# new_inverter.net
KiCad netlist of a schematic drawn in EAGLE
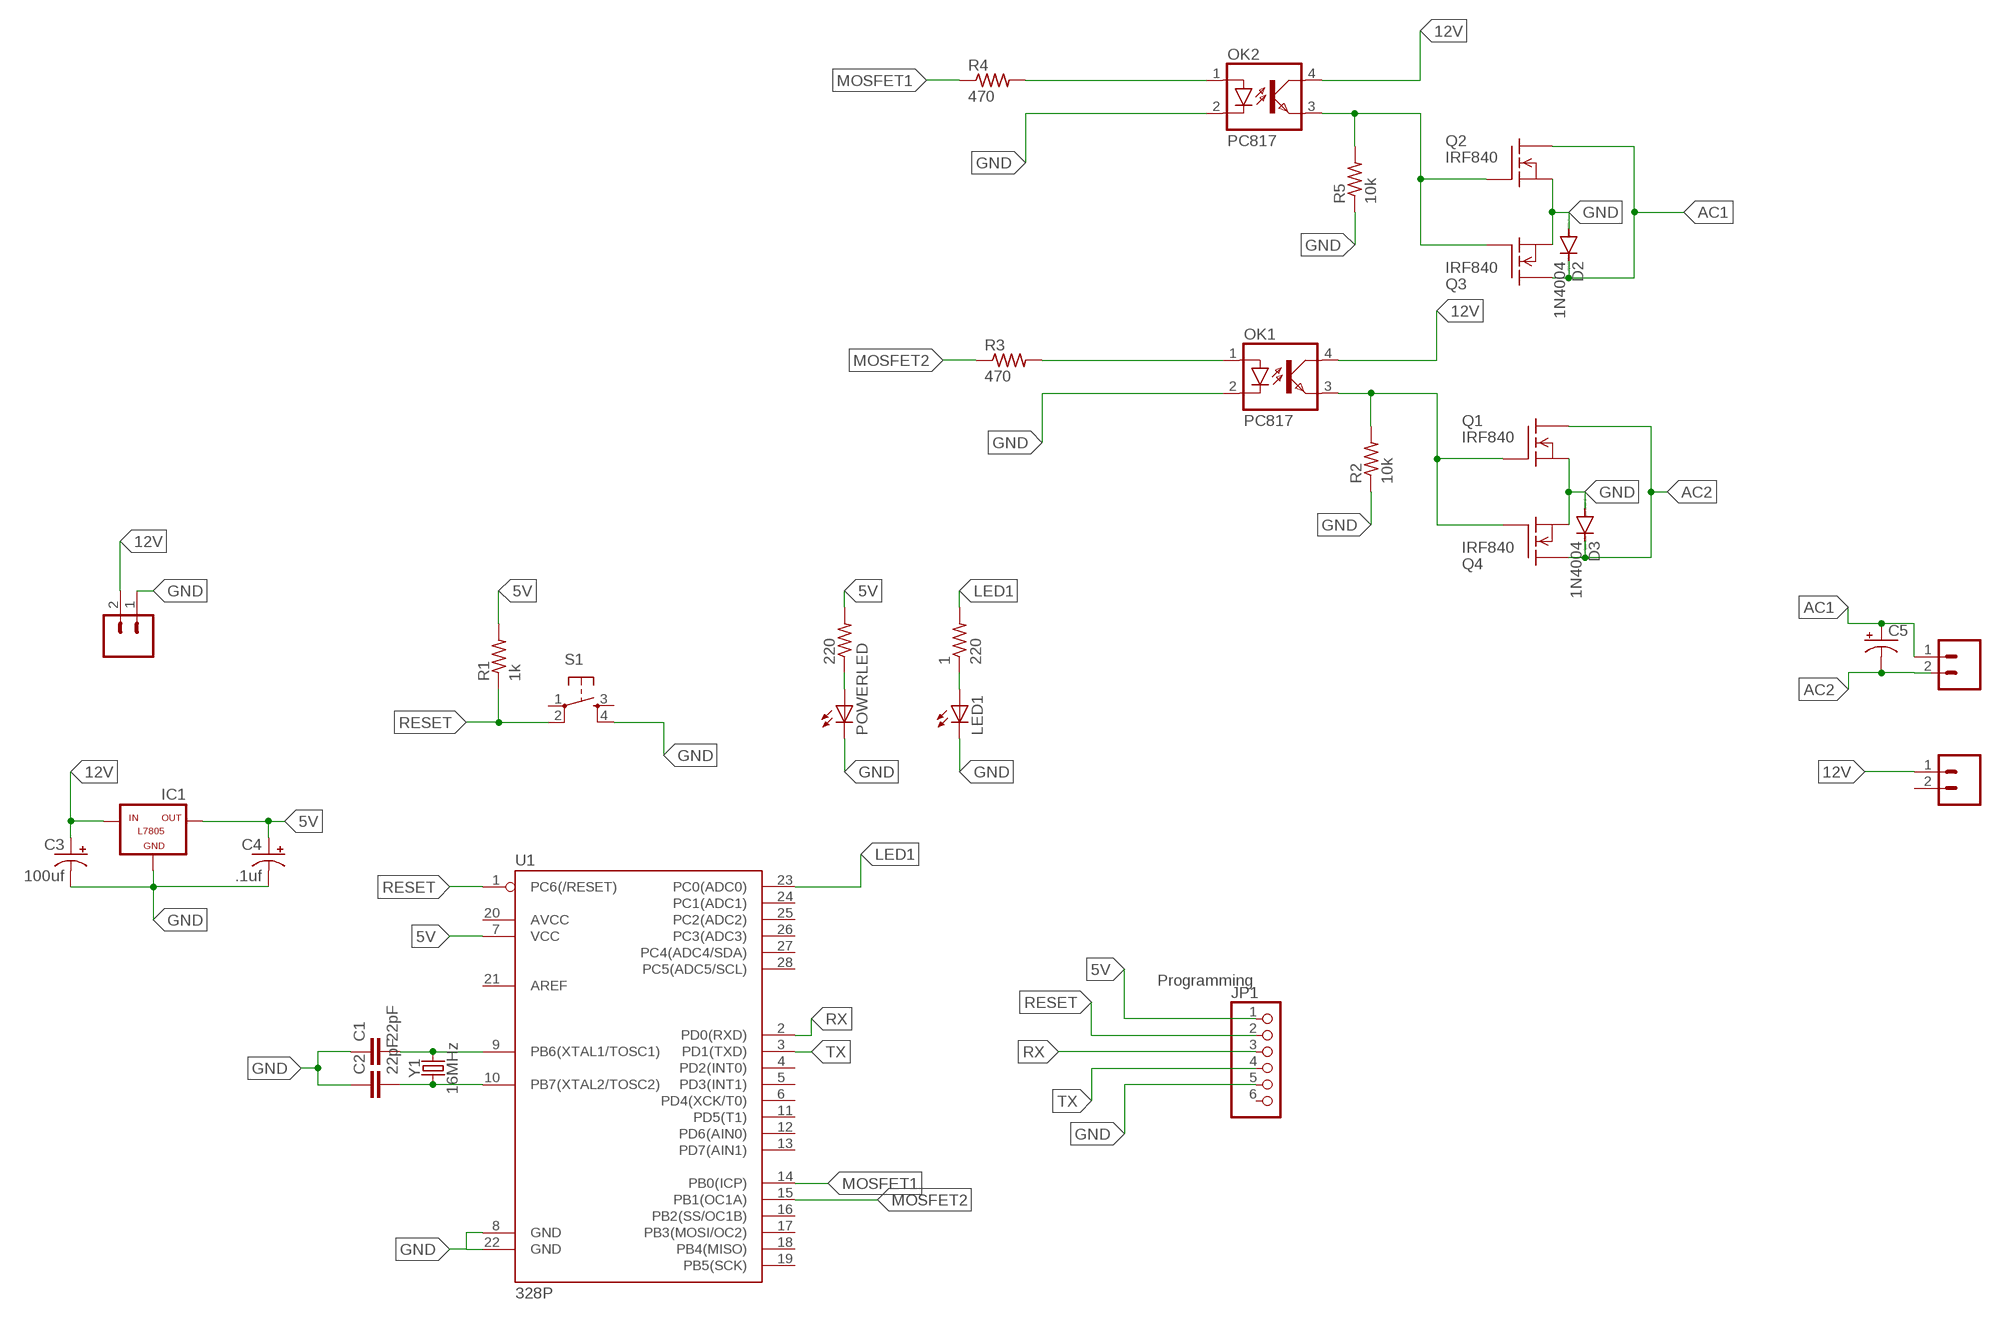
[diagram p0: schematic, sheet 1]

(export (version "E")
  (design (tool "Eeschema 10.0.6"))
  (components
    (comp (ref "1")
      (value "220")
      (footprint "eagle-import:0204_5")
      (libsource (lib "eagle-import") (part "R-US_0204/5"))
    )
    (comp (ref "220")
      (value "R-US_0204/5")
      (footprint "eagle-import:0204_5")
      (libsource (lib "eagle-import") (part "R-US_0204/5"))
    )
    (comp (ref "C1")
      (value "22pF")
      (footprint "eagle-import:CAP-PTH-2.54")
      (libsource (lib "eagle-import") (part "22PF-PTH-2.54MM-200V-5%"))
    )
    (comp (ref "C2")
      (value "22pF")
      (footprint "eagle-import:CAP-PTH-2.54")
      (libsource (lib "eagle-import") (part "22PF-PTH-2.54MM-200V-5%"))
    )
    (comp (ref "C3")
      (value "100uf")
      (footprint "eagle-import:E5-5")
      (libsource (lib "eagle-import") (part "CPOL-USE5-5"))
    )
    (comp (ref "C4")
      (value ".1uf")
      (footprint "eagle-import:E5-5")
      (libsource (lib "eagle-import") (part "CPOL-USE5-5"))
    )
    (comp (ref "C5")
      (value "CPOL-USE5-13")
      (footprint "eagle-import:E5-13")
      (libsource (lib "eagle-import") (part "CPOL-USE5-13"))
    )
    (comp (ref "D2")
      (value "1N4004")
      (footprint "eagle-import:DO41-10")
      (libsource (lib "eagle-import") (part "1N4004"))
    )
    (comp (ref "D3")
      (value "1N4004")
      (footprint "eagle-import:DO41-10")
      (libsource (lib "eagle-import") (part "1N4004"))
    )
    (comp (ref "IC1")
      (value "L7805")
      (footprint "eagle-import:78XXL")
      (libsource (lib "eagle-import") (part "L7805"))
    )
    (comp (ref "J1")
      (value "CONN_025MM")
      (footprint "eagle-import:SCREWTERMINAL-5MM-2")
      (libsource (lib "eagle-import") (part "CONN_025MM"))
    )
    (comp (ref "J2")
      (value "CONN_025MM")
      (footprint "eagle-import:SCREWTERMINAL-5MM-2")
      (libsource (lib "eagle-import") (part "CONN_025MM"))
    )
    (comp (ref "J3")
      (value "CONN_025MM")
      (footprint "eagle-import:SCREWTERMINAL-5MM-2")
      (libsource (lib "eagle-import") (part "CONN_025MM"))
    )
    (comp (ref "JP1")
      (value "PINHD-1X6")
      (footprint "eagle-import:1X06")
      (libsource (lib "eagle-import") (part "PINHD-1X6"))
    )
    (comp (ref "LED1")
      (value "LED5MM")
      (footprint "eagle-import:LED5MM")
      (libsource (lib "eagle-import") (part "LED5MM"))
    )
    (comp (ref "OK1")
      (value "PC817")
      (footprint "eagle-import:DIL04")
      (fields (field (name "MPN") "PC817X4J000F"))
      (libsource (lib "eagle-import") (part "PC817"))
    )
    (comp (ref "OK2")
      (value "PC817")
      (footprint "eagle-import:DIL04")
      (fields (field (name "MPN") "PC817X4J000F"))
      (libsource (lib "eagle-import") (part "PC817"))
    )
    (comp (ref "POWERLED")
      (value "LED5MM")
      (footprint "eagle-import:LED5MM")
      (libsource (lib "eagle-import") (part "LED5MM"))
    )
    (comp (ref "Q1")
      (value "IRF840")
      (footprint "eagle-import:TO220")
      (libsource (lib "eagle-import") (part "IRF840"))
    )
    (comp (ref "Q2")
      (value "IRF840")
      (footprint "eagle-import:TO220")
      (libsource (lib "eagle-import") (part "IRF840"))
    )
    (comp (ref "Q3")
      (value "IRF840")
      (footprint "eagle-import:TO220")
      (libsource (lib "eagle-import") (part "IRF840"))
    )
    (comp (ref "Q4")
      (value "IRF840")
      (footprint "eagle-import:TO220")
      (libsource (lib "eagle-import") (part "IRF840"))
    )
    (comp (ref "R1")
      (value "1k")
      (footprint "eagle-import:0204_5")
      (libsource (lib "eagle-import") (part "R-US_0204/5"))
    )
    (comp (ref "R2")
      (value "10k")
      (footprint "eagle-import:0204_5")
      (libsource (lib "eagle-import") (part "R-US_0204/5"))
    )
    (comp (ref "R3")
      (value "470")
      (footprint "eagle-import:0204_5")
      (libsource (lib "eagle-import") (part "R-US_0204/5"))
    )
    (comp (ref "R4")
      (value "470")
      (footprint "eagle-import:0204_5")
      (libsource (lib "eagle-import") (part "R-US_0204/5"))
    )
    (comp (ref "R5")
      (value "10k")
      (footprint "eagle-import:0204_5")
      (libsource (lib "eagle-import") (part "R-US_0204/5"))
    )
    (comp (ref "S1")
      (value "TAC_SWITCHPTH")
      (footprint "eagle-import:TACTILE-PTH")
      (libsource (lib "eagle-import") (part "TAC_SWITCHPTH"))
    )
    (comp (ref "U1")
      (value "328P")
      (footprint "eagle-import:DIP28")
      (libsource (lib "eagle-import") (part "ATMEGA328P_PDIP"))
    )
    (comp (ref "Y1")
      (value "16MHz")
      (footprint "eagle-import:HC49US")
      (libsource (lib "eagle-import") (part "CRYSTAL-16MHZPTH-HC49US"))
    )
  )
  (nets
    (net (code "1") (name "5V") (class "Default")
      (node (ref "220") (pin "2") (pinfunction "2_2") (pintype "passive"))
      (node (ref "C4") (pin "+") (pinfunction "+_+") (pintype "passive"))
      (node (ref "IC1") (pin "OUT") (pinfunction "OUT_OUT") (pintype "passive"))
      (node (ref "JP1") (pin "1") (pinfunction "1_1") (pintype "passive"))
      (node (ref "R1") (pin "2") (pinfunction "2_2") (pintype "passive"))
      (node (ref "U1") (pin "7") (pinfunction "VCC_7") (pintype "bidirectional"))
    )
    (net (code "2") (name "12V") (class "Default")
      (node (ref "C3") (pin "+") (pinfunction "+_+") (pintype "passive"))
      (node (ref "IC1") (pin "IN") (pinfunction "IN_IN") (pintype "input"))
      (node (ref "J1") (pin "2") (pinfunction "2_2") (pintype "passive"))
      (node (ref "J2") (pin "1") (pinfunction "1_1") (pintype "passive"))
      (node (ref "OK1") (pin "4") (pinfunction "COL_4") (pintype "passive"))
      (node (ref "OK2") (pin "4") (pinfunction "COL_4") (pintype "passive"))
    )
    (net (code "3") (name "AC1") (class "Default")
      (node (ref "C5") (pin "+") (pinfunction "+_+") (pintype "passive"))
      (node (ref "D2") (pin "C") (pinfunction "C_C") (pintype "passive"))
      (node (ref "J3") (pin "1") (pinfunction "1_1") (pintype "passive"))
      (node (ref "Q2") (pin "2") (pinfunction "D_2") (pintype "passive"))
      (node (ref "Q3") (pin "2") (pinfunction "D_2") (pintype "passive"))
    )
    (net (code "4") (name "AC2") (class "Default")
      (node (ref "C5") (pin "-") (pinfunction "-_-") (pintype "passive"))
      (node (ref "D3") (pin "C") (pinfunction "C_C") (pintype "passive"))
      (node (ref "J3") (pin "2") (pinfunction "2_2") (pintype "passive"))
      (node (ref "Q1") (pin "2") (pinfunction "D_2") (pintype "passive"))
      (node (ref "Q4") (pin "2") (pinfunction "D_2") (pintype "passive"))
    )
    (net (code "5") (name "GND") (class "Default")
      (node (ref "C1") (pin "1") (pinfunction "1_1") (pintype "passive"))
      (node (ref "C2") (pin "1") (pinfunction "1_1") (pintype "passive"))
      (node (ref "C3") (pin "-") (pinfunction "-_-") (pintype "passive"))
      (node (ref "C4") (pin "-") (pinfunction "-_-") (pintype "passive"))
      (node (ref "D2") (pin "A") (pinfunction "A_A") (pintype "passive"))
      (node (ref "D3") (pin "A") (pinfunction "A_A") (pintype "passive"))
      (node (ref "IC1") (pin "GND") (pinfunction "GND_GND") (pintype "input"))
      (node (ref "J1") (pin "1") (pinfunction "1_1") (pintype "passive"))
      (node (ref "JP1") (pin "5") (pinfunction "5_5") (pintype "passive"))
      (node (ref "LED1") (pin "K") (pinfunction "C_K") (pintype "passive"))
      (node (ref "OK1") (pin "2") (pinfunction "C_2") (pintype "passive"))
      (node (ref "OK2") (pin "2") (pinfunction "C_2") (pintype "passive"))
      (node (ref "POWERLED") (pin "K") (pinfunction "C_K") (pintype "passive"))
      (node (ref "Q1") (pin "3") (pinfunction "S_3") (pintype "passive"))
      (node (ref "Q2") (pin "3") (pinfunction "S_3") (pintype "passive"))
      (node (ref "Q3") (pin "3") (pinfunction "S_3") (pintype "passive"))
      (node (ref "Q4") (pin "3") (pinfunction "S_3") (pintype "passive"))
      (node (ref "R2") (pin "1") (pinfunction "1_1") (pintype "passive"))
      (node (ref "R5") (pin "1") (pinfunction "1_1") (pintype "passive"))
      (node (ref "S1") (pin "4") (pinfunction "4_4") (pintype "passive"))
      (node (ref "U1") (pin "22") (pinfunction "GND_22") (pintype "bidirectional"))
      (node (ref "U1") (pin "8") (pinfunction "GND_8") (pintype "bidirectional"))
    )
    (net (code "6") (name "LED1") (class "Default")
      (node (ref "1") (pin "2") (pinfunction "2_2") (pintype "passive"))
      (node (ref "U1") (pin "23") (pinfunction "PC0(ADC0)_23") (pintype "bidirectional"))
    )
    (net (code "7") (name "MOSFET1") (class "Default")
      (node (ref "R4") (pin "1") (pinfunction "1_1") (pintype "passive"))
      (node (ref "U1") (pin "14") (pinfunction "PB0(ICP)_14") (pintype "bidirectional"))
    )
    (net (code "8") (name "MOSFET2") (class "Default")
      (node (ref "R3") (pin "1") (pinfunction "1_1") (pintype "passive"))
      (node (ref "U1") (pin "15") (pinfunction "PB1(OC1A)_15") (pintype "bidirectional"))
    )
    (net (code "9") (name "Net-(1-Pad1)") (class "Default")
      (node (ref "1") (pin "1") (pinfunction "1_1") (pintype "passive"))
      (node (ref "LED1") (pin "A") (pinfunction "A_A") (pintype "passive"))
    )
    (net (code "10") (name "Net-(220-Pad1)") (class "Default")
      (node (ref "220") (pin "1") (pinfunction "1_1") (pintype "passive"))
      (node (ref "POWERLED") (pin "A") (pinfunction "A_A") (pintype "passive"))
    )
    (net (code "11") (name "Net-(OK1-A)") (class "Default")
      (node (ref "OK1") (pin "1") (pinfunction "A_1") (pintype "passive"))
      (node (ref "R3") (pin "2") (pinfunction "2_2") (pintype "passive"))
    )
    (net (code "12") (name "Net-(OK1-EMIT)") (class "Default")
      (node (ref "OK1") (pin "3") (pinfunction "EMIT_3") (pintype "passive"))
      (node (ref "Q1") (pin "1") (pinfunction "G_1") (pintype "passive"))
      (node (ref "Q4") (pin "1") (pinfunction "G_1") (pintype "passive"))
      (node (ref "R2") (pin "2") (pinfunction "2_2") (pintype "passive"))
    )
    (net (code "13") (name "Net-(OK2-A)") (class "Default")
      (node (ref "OK2") (pin "1") (pinfunction "A_1") (pintype "passive"))
      (node (ref "R4") (pin "2") (pinfunction "2_2") (pintype "passive"))
    )
    (net (code "14") (name "Net-(OK2-EMIT)") (class "Default")
      (node (ref "OK2") (pin "3") (pinfunction "EMIT_3") (pintype "passive"))
      (node (ref "Q2") (pin "1") (pinfunction "G_1") (pintype "passive"))
      (node (ref "Q3") (pin "1") (pinfunction "G_1") (pintype "passive"))
      (node (ref "R5") (pin "2") (pinfunction "2_2") (pintype "passive"))
    )
    (net (code "15") (name "Net-(U1-PB6(XTAL1{slash}TOSC1))") (class "Default")
      (node (ref "C1") (pin "2") (pinfunction "2_2") (pintype "passive"))
      (node (ref "U1") (pin "9") (pinfunction "PB6(XTAL1/TOSC1)_9") (pintype "bidirectional"))
      (node (ref "Y1") (pin "2") (pinfunction "2_2") (pintype "passive"))
    )
    (net (code "16") (name "Net-(U1-PB7(XTAL2{slash}TOSC2))") (class "Default")
      (node (ref "C2") (pin "2") (pinfunction "2_2") (pintype "passive"))
      (node (ref "U1") (pin "10") (pinfunction "PB7(XTAL2/TOSC2)_10") (pintype "bidirectional"))
      (node (ref "Y1") (pin "1") (pinfunction "1_1") (pintype "passive"))
    )
    (net (code "17") (name "RESET") (class "Default")
      (node (ref "JP1") (pin "2") (pinfunction "2_2") (pintype "passive"))
      (node (ref "R1") (pin "1") (pinfunction "1_1") (pintype "passive"))
      (node (ref "S1") (pin "2") (pinfunction "2_2") (pintype "passive"))
      (node (ref "U1") (pin "1") (pinfunction "PC6(/RESET)_1") (pintype "bidirectional"))
    )
    (net (code "18") (name "RX") (class "Default")
      (node (ref "JP1") (pin "3") (pinfunction "3_3") (pintype "passive"))
      (node (ref "U1") (pin "2") (pinfunction "PD0(RXD)_2") (pintype "bidirectional"))
    )
    (net (code "19") (name "TX") (class "Default")
      (node (ref "JP1") (pin "4") (pinfunction "4_4") (pintype "passive"))
      (node (ref "U1") (pin "3") (pinfunction "PD1(TXD)_3") (pintype "bidirectional"))
    )
    (net (code "20") (name "unconnected-(J2-Pad2)") (class "Default")
      (node (ref "J2") (pin "2") (pinfunction "2_2") (pintype "passive"))
    )
    (net (code "21") (name "unconnected-(JP1-Pad6)") (class "Default")
      (node (ref "JP1") (pin "6") (pinfunction "6_6") (pintype "passive"))
    )
    (net (code "22") (name "unconnected-(S1-Pad1)") (class "Default")
      (node (ref "S1") (pin "1") (pinfunction "1_1") (pintype "passive"))
    )
    (net (code "23") (name "unconnected-(S1-Pad3)") (class "Default")
      (node (ref "S1") (pin "3") (pinfunction "3_3") (pintype "passive"))
    )
    (net (code "24") (name "unconnected-(U1-AREF-Pad21)") (class "Default")
      (node (ref "U1") (pin "21") (pinfunction "AREF_21") (pintype "bidirectional"))
    )
    (net (code "25") (name "unconnected-(U1-AVCC-Pad20)") (class "Default")
      (node (ref "U1") (pin "20") (pinfunction "AVCC_20") (pintype "bidirectional"))
    )
    (net (code "26") (name "unconnected-(U1-PB2(SS{slash}OC1B)-Pad16)") (class "Default")
      (node (ref "U1") (pin "16") (pinfunction "PB2(SS/OC1B)_16") (pintype "bidirectional"))
    )
    (net (code "27") (name "unconnected-(U1-PB3(MOSI{slash}OC2)-Pad17)") (class "Default")
      (node (ref "U1") (pin "17") (pinfunction "PB3(MOSI/OC2)_17") (pintype "bidirectional"))
    )
    (net (code "28") (name "unconnected-(U1-PB4(MISO)-Pad18)") (class "Default")
      (node (ref "U1") (pin "18") (pinfunction "PB4(MISO)_18") (pintype "bidirectional"))
    )
    (net (code "29") (name "unconnected-(U1-PB5(SCK)-Pad19)") (class "Default")
      (node (ref "U1") (pin "19") (pinfunction "PB5(SCK)_19") (pintype "bidirectional"))
    )
    (net (code "30") (name "unconnected-(U1-PC1(ADC1)-Pad24)") (class "Default")
      (node (ref "U1") (pin "24") (pinfunction "PC1(ADC1)_24") (pintype "bidirectional"))
    )
    (net (code "31") (name "unconnected-(U1-PC2(ADC2)-Pad25)") (class "Default")
      (node (ref "U1") (pin "25") (pinfunction "PC2(ADC2)_25") (pintype "bidirectional"))
    )
    (net (code "32") (name "unconnected-(U1-PC3(ADC3)-Pad26)") (class "Default")
      (node (ref "U1") (pin "26") (pinfunction "PC3(ADC3)_26") (pintype "bidirectional"))
    )
    (net (code "33") (name "unconnected-(U1-PC4(ADC4{slash}SDA)-Pad27)") (class "Default")
      (node (ref "U1") (pin "27") (pinfunction "PC4(ADC4/SDA)_27") (pintype "bidirectional"))
    )
    (net (code "34") (name "unconnected-(U1-PC5(ADC5{slash}SCL)-Pad28)") (class "Default")
      (node (ref "U1") (pin "28") (pinfunction "PC5(ADC5/SCL)_28") (pintype "bidirectional"))
    )
    (net (code "35") (name "unconnected-(U1-PD2(INT0)-Pad4)") (class "Default")
      (node (ref "U1") (pin "4") (pinfunction "PD2(INT0)_4") (pintype "bidirectional"))
    )
    (net (code "36") (name "unconnected-(U1-PD3(INT1)-Pad5)") (class "Default")
      (node (ref "U1") (pin "5") (pinfunction "PD3(INT1)_5") (pintype "bidirectional"))
    )
    (net (code "37") (name "unconnected-(U1-PD4(XCK{slash}T0)-Pad6)") (class "Default")
      (node (ref "U1") (pin "6") (pinfunction "PD4(XCK/T0)_6") (pintype "bidirectional"))
    )
    (net (code "38") (name "unconnected-(U1-PD5(T1)-Pad11)") (class "Default")
      (node (ref "U1") (pin "11") (pinfunction "PD5(T1)_11") (pintype "bidirectional"))
    )
    (net (code "39") (name "unconnected-(U1-PD6(AIN0)-Pad12)") (class "Default")
      (node (ref "U1") (pin "12") (pinfunction "PD6(AIN0)_12") (pintype "bidirectional"))
    )
    (net (code "40") (name "unconnected-(U1-PD7(AIN1)-Pad13)") (class "Default")
      (node (ref "U1") (pin "13") (pinfunction "PD7(AIN1)_13") (pintype "bidirectional"))
    )
  )
)
